# top.net
KiCad netlist of a schematic drawn in Altium Designer
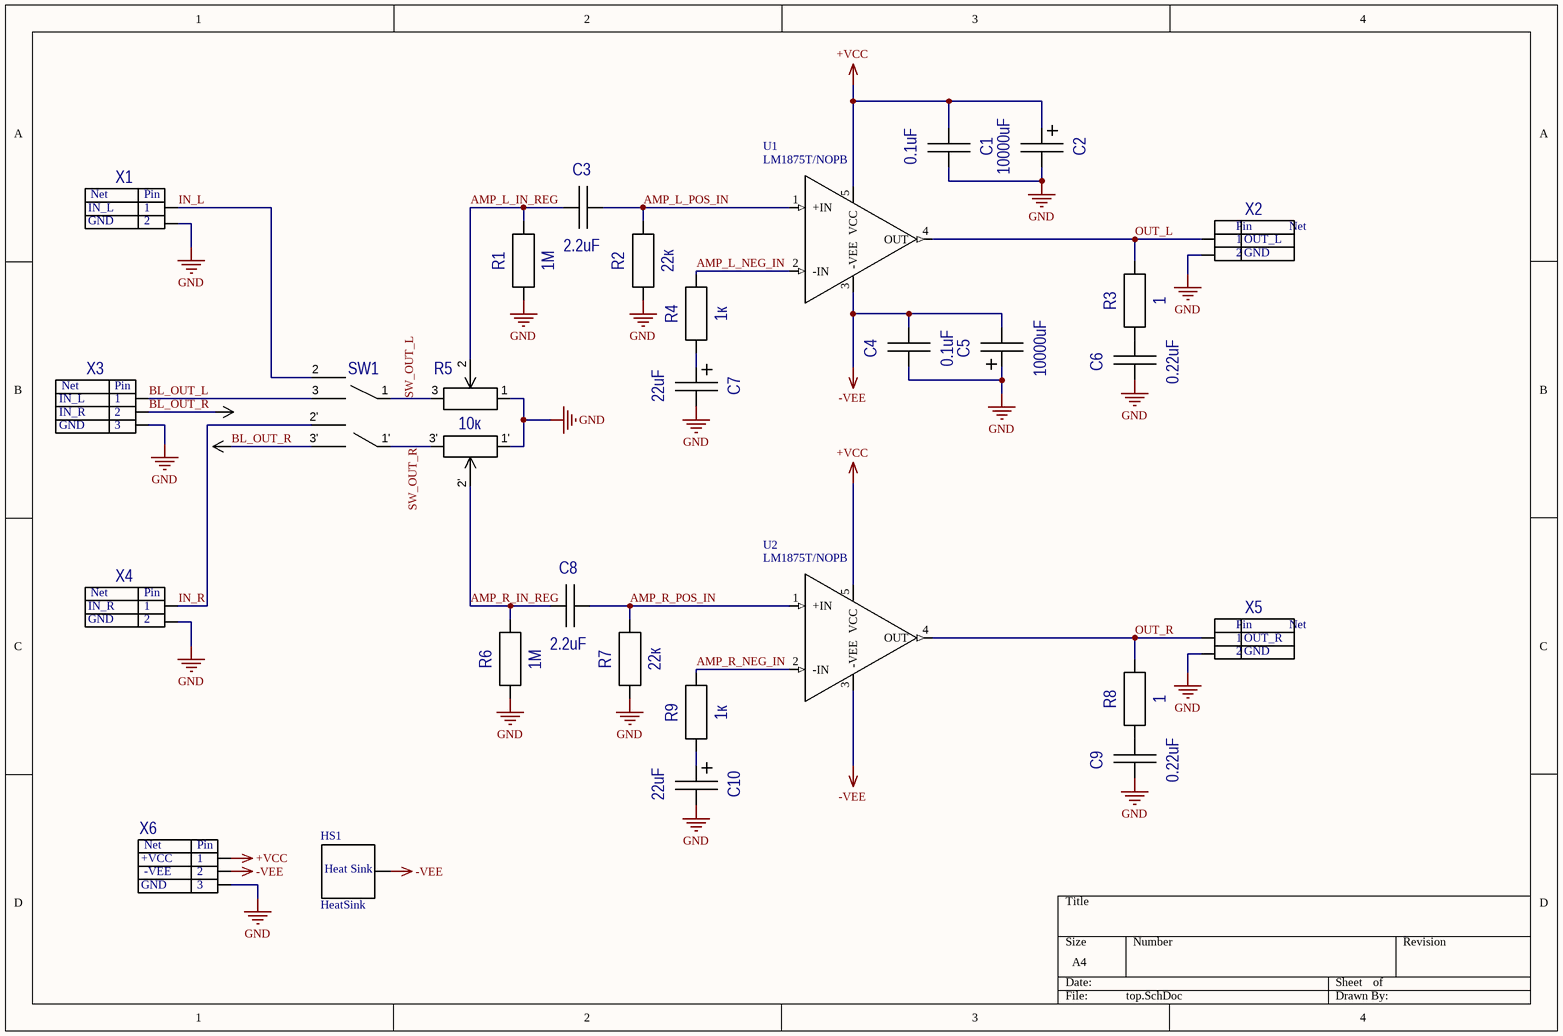
[diagram p0: top.SchDoc]

(export (version "E")
  (design (tool "Eeschema 10.0.6"))
  (components
    (comp (ref "C1")
      (value "0.1uF")
      (footprint "capK73-17")
      (description "26320")
      (libsource (lib "Schlib1") (part "К73-17, 0.1 мкФ, 250 В, 5%"))
    )
    (comp (ref "C2")
      (value "10000uF")
      (footprint "Capacitor_SnapIn_35x50mm")
      (description "26320")
      (libsource (lib "Schlib1") (part "ECAP (К50-35), 10000 мкФ, 50 В, 105°C, 20%"))
    )
    (comp (ref "C3")
      (value "2.2uF")
      (footprint "capK73-17")
      (description "8016")
      (libsource (lib "Schlib1") (part "К73-17, 2.2 мкФ, 63 В, 5%"))
    )
    (comp (ref "C4")
      (value "0.1uF")
      (footprint "capK73-17")
      (description "26320")
      (libsource (lib "Schlib1") (part "К73-17, 0.1 мкФ, 250 В, 5%"))
    )
    (comp (ref "C5")
      (value "10000uF")
      (footprint "Capacitor_SnapIn_35x50mm")
      (description "26320")
      (libsource (lib "Schlib1") (part "ECAP (К50-35), 10000 мкФ, 50 В, 105°C, 20%"))
    )
    (comp (ref "C6")
      (value "0.22uF")
      (footprint "capK73-17")
      (description "61862")
      (libsource (lib "Schlib1") (part "К73-17, 0.22 мкФ, 63 В, 5%"))
    )
    (comp (ref "C7")
      (value "22uF")
      (footprint "capRadial6.3x12mmP:2.5mm")
      (description "9000565851")
      (libsource (lib "Schlib1") (part "ECAP (К50-35), 10000 мкФ, 50 В, 105°C, 20%_1"))
    )
    (comp (ref "C8")
      (value "2.2uF")
      (footprint "capK73-17")
      (description "8016")
      (libsource (lib "Schlib1") (part "К73-17, 2.2 мкФ, 63 В, 5%"))
    )
    (comp (ref "C9")
      (value "0.22uF")
      (footprint "capK73-17")
      (description "61862")
      (libsource (lib "Schlib1") (part "К73-17, 0.22 мкФ, 63 В, 5%"))
    )
    (comp (ref "C10")
      (value "22uF")
      (footprint "capRadial6.3x12mmP:2.5mm")
      (description "9000565851")
      (libsource (lib "Schlib1") (part "ECAP (К50-35), 10000 мкФ, 50 В, 105°C, 20%_1"))
    )
    (comp (ref "HS1") (value "HeatSink") (footprint "HeatSink") (libsource (lib "Schlib1") (part "HeatSink")))
    (comp (ref "R1")
      (value "1М")
      (footprint "res0.25W/1M/0.5pitch")
      (description "51741")
      (libsource (lib "Schlib1") (part "CF-25 (С1-4) 0.25 Вт, 1 МОм, 5%"))
    )
    (comp (ref "R2")
      (value "22к")
      (footprint "res0.25W/22k/400mil")
      (description "8007031688")
      (libsource (lib "Schlib1") (part "1/4W22K, Резистор угольный 1/4Вт 22 кОм 2,5X7мм 5%"))
    )
    (comp (ref "R3")
      (value "1")
      (footprint "res1W/1/700mil")
      (description "24035")
      (libsource (lib "Schlib1") (part "MO-100 (С2-23) 1 Вт, 1 Ом, 5%"))
    )
    (comp (ref "R4")
      (value "1к")
      (footprint "res0.25W/1k/400mil")
      (description "44435")
      (libsource (lib "Schlib1") (part "CF-25 (С1-4) 0.25 Вт, 1 кОм, 5%"))
    )
    (comp (ref "R5")
      (value "10к")
      (footprint "dualVarRes")
      (description "588623436")
      (libsource (lib "Schlib1") (part "RK-1233G1-A10K, L15KC, 2 х 10 кОм"))
    )
    (comp (ref "R6")
      (value "1М")
      (footprint "res0.25W/1M/0.5pitch")
      (description "51741")
      (libsource (lib "Schlib1") (part "CF-25 (С1-4) 0.25 Вт, 1 МОм, 5%"))
    )
    (comp (ref "R7")
      (value "22к")
      (footprint "res0.25W/22k/400mil")
      (description "8007031688")
      (libsource (lib "Schlib1") (part "1/4W22K, Резистор угольный 1/4Вт 22 кОм 2,5X7мм 5%"))
    )
    (comp (ref "R8")
      (value "1")
      (footprint "res1W/1/700mil")
      (description "24035")
      (libsource (lib "Schlib1") (part "MO-100 (С2-23) 1 Вт, 1 Ом, 5%"))
    )
    (comp (ref "R9")
      (value "1к")
      (footprint "res0.25W/1k/400mil")
      (description "44435")
      (libsource (lib "Schlib1") (part "CF-25 (С1-4) 0.25 Вт, 1 кОм, 5%"))
    )
    (comp (ref "SW1") (value "~") (footprint "dualVarRes") (libsource (lib "Schlib1") (part "SWITCHER")))
    (comp (ref "U1")
      (value "LM1875T/NOPB")
      (footprint "TO220-5/2.54")
      (description "12717")
      (libsource (lib "Schlib1") (part "LM1875T/NOPB"))
    )
    (comp (ref "U2")
      (value "LM1875T/NOPB")
      (footprint "TO220-5/2.54")
      (description "12717")
      (libsource (lib "Schlib1") (part "LM1875T/NOPB"))
    )
    (comp (ref "X1")
      (value "~")
      (footprint "BUTTON_template")
      (description "Generic connector")
      (fields (field (name "PARAMETER 2") "IN_L") (field (name "PARAMETER 1") "GND"))
      (libsource (lib "Schlib1") (part "2pinConnector"))
    )
    (comp (ref "X2")
      (value "~")
      (footprint "BUTTON_template")
      (description "Generic connector")
      (fields (field (name "PARAMETER 2") "OUT_L") (field (name "PARAMETER 1") "GND"))
      (libsource (lib "Schlib1") (part "2pinConnector"))
    )
    (comp (ref "X3")
      (value "~")
      (footprint "3pim2.54Connector")
      (description "Input from Bluetooth module")
      (libsource (lib "Schlib1") (part "BluetoothModule"))
    )
    (comp (ref "X4")
      (value "~")
      (footprint "BUTTON_template")
      (description "Generic connector")
      (fields (field (name "PARAMETER 2") "IN_R") (field (name "PARAMETER 1") "GND"))
      (libsource (lib "Schlib1") (part "2pinConnector"))
    )
    (comp (ref "X5")
      (value "~")
      (footprint "BUTTON_template")
      (description "Generic connector")
      (fields (field (name "PARAMETER 2") "OUT_R") (field (name "PARAMETER 1") "GND"))
      (libsource (lib "Schlib1") (part "2pinConnector"))
    )
    (comp (ref "X6")
      (value "~")
      (footprint "3pim2.54Connector")
      (description "Generic connector")
      (fields
        (field (name "PARAMETER 3") "+VCC")
        (field (name "PARAMETER 2") "-VEE")
        (field (name "PARAMETER 1") "GND")
      )
      (libsource (lib "Schlib1") (part "3pinConnector"))
    )
  )
  (nets
    (net (code "1") (name "+VCC") (class "Default")
      (node (ref "C1") (pin "1") (pinfunction "1_1") (pintype "passive"))
      (node (ref "C2") (pin "1") (pinfunction "+_1") (pintype "passive"))
      (node (ref "U1") (pin "5") (pinfunction "VCC_5") (pintype "power_in"))
      (node (ref "U2") (pin "5") (pinfunction "VCC_5") (pintype "power_in"))
      (node (ref "X6") (pin "1") (pinfunction "1_1") (pintype "passive"))
    )
    (net (code "2") (name "-VEE") (class "Default")
      (node (ref "C4") (pin "2") (pinfunction "2_2") (pintype "passive"))
      (node (ref "C5") (pin "2") (pinfunction "-_2") (pintype "passive"))
      (node (ref "HS1") (pin "1") (pinfunction "HS_1") (pintype "power_in"))
      (node (ref "U1") (pin "3") (pinfunction "-VEE_3") (pintype "power_in"))
      (node (ref "U2") (pin "3") (pinfunction "-VEE_3") (pintype "power_in"))
      (node (ref "X6") (pin "2") (pinfunction "2_2") (pintype "passive"))
    )
    (net (code "3") (name "/AMP_L_IN_REG") (class "Default")
      (node (ref "C3") (pin "1") (pinfunction "1_1") (pintype "passive"))
      (node (ref "R1") (pin "2") (pinfunction "2_2") (pintype "passive"))
      (node (ref "R5") (pin "2") (pinfunction "2_2") (pintype "passive"))
    )
    (net (code "4") (name "/AMP_L_NEG_IN") (class "Default")
      (node (ref "R4") (pin "2") (pinfunction "2_2") (pintype "passive"))
      (node (ref "U1") (pin "2") (pinfunction "-IN_2") (pintype "input"))
    )
    (net (code "5") (name "/AMP_L_POS_IN") (class "Default")
      (node (ref "C3") (pin "2") (pinfunction "2_2") (pintype "passive"))
      (node (ref "R2") (pin "2") (pinfunction "2_2") (pintype "passive"))
      (node (ref "U1") (pin "1") (pinfunction "+IN_1") (pintype "input"))
    )
    (net (code "6") (name "/AMP_R_IN_REG") (class "Default")
      (node (ref "C8") (pin "1") (pinfunction "1_1") (pintype "passive"))
      (node (ref "R5") (pin "2'") (pinfunction "2'_2'") (pintype "passive"))
      (node (ref "R6") (pin "2") (pinfunction "2_2") (pintype "passive"))
    )
    (net (code "7") (name "/AMP_R_NEG_IN") (class "Default")
      (node (ref "R9") (pin "2") (pinfunction "2_2") (pintype "passive"))
      (node (ref "U2") (pin "2") (pinfunction "-IN_2") (pintype "input"))
    )
    (net (code "8") (name "/AMP_R_POS_IN") (class "Default")
      (node (ref "C8") (pin "2") (pinfunction "2_2") (pintype "passive"))
      (node (ref "R7") (pin "2") (pinfunction "2_2") (pintype "passive"))
      (node (ref "U2") (pin "1") (pinfunction "+IN_1") (pintype "input"))
    )
    (net (code "9") (name "/BL_OUT_L") (class "Default")
      (node (ref "SW1") (pin "3") (pinfunction "3_3") (pintype "passive"))
      (node (ref "X3") (pin "1") (pinfunction "1_1") (pintype "passive"))
    )
    (net (code "10") (name "/BL_OUT_R") (class "Default")
      (node (ref "SW1") (pin "3'") (pinfunction "3'_3'") (pintype "passive"))
      (node (ref "X3") (pin "2") (pinfunction "2_2") (pintype "passive"))
    )
    (net (code "11") (name "/IN_L") (class "Default")
      (node (ref "SW1") (pin "2") (pinfunction "2_2") (pintype "passive"))
      (node (ref "X1") (pin "1") (pinfunction "1_1") (pintype "passive"))
    )
    (net (code "12") (name "/IN_R") (class "Default")
      (node (ref "SW1") (pin "2'") (pinfunction "2'_2'") (pintype "passive"))
      (node (ref "X4") (pin "1") (pinfunction "1_1") (pintype "passive"))
    )
    (net (code "13") (name "/OUT_L") (class "Default")
      (node (ref "R3") (pin "2") (pinfunction "2_2") (pintype "passive"))
      (node (ref "U1") (pin "4") (pinfunction "OUT_4") (pintype "output"))
      (node (ref "X2") (pin "1") (pinfunction "1_1") (pintype "passive"))
    )
    (net (code "14") (name "/OUT_R") (class "Default")
      (node (ref "R8") (pin "2") (pinfunction "2_2") (pintype "passive"))
      (node (ref "U2") (pin "4") (pinfunction "OUT_4") (pintype "output"))
      (node (ref "X5") (pin "1") (pinfunction "1_1") (pintype "passive"))
    )
    (net (code "15") (name "/SW_OUT_L") (class "Default")
      (node (ref "R5") (pin "3") (pinfunction "3_3") (pintype "passive"))
      (node (ref "SW1") (pin "1") (pinfunction "1_1") (pintype "passive"))
    )
    (net (code "16") (name "/SW_OUT_R") (class "Default")
      (node (ref "R5") (pin "3'") (pinfunction "3'_3'") (pintype "passive"))
      (node (ref "SW1") (pin "1'") (pinfunction "1'_1'") (pintype "passive"))
    )
    (net (code "17") (name "GND") (class "Default")
      (node (ref "C1") (pin "2") (pinfunction "2_2") (pintype "passive"))
      (node (ref "C10") (pin "2") (pinfunction "-_2") (pintype "passive"))
      (node (ref "C2") (pin "2") (pinfunction "-_2") (pintype "passive"))
      (node (ref "C4") (pin "1") (pinfunction "1_1") (pintype "passive"))
      (node (ref "C5") (pin "1") (pinfunction "+_1") (pintype "passive"))
      (node (ref "C6") (pin "1") (pinfunction "1_1") (pintype "passive"))
      (node (ref "C7") (pin "2") (pinfunction "-_2") (pintype "passive"))
      (node (ref "C9") (pin "1") (pinfunction "1_1") (pintype "passive"))
      (node (ref "R1") (pin "1") (pinfunction "1_1") (pintype "passive"))
      (node (ref "R2") (pin "1") (pinfunction "1_1") (pintype "passive"))
      (node (ref "R5") (pin "1") (pinfunction "1_1") (pintype "passive"))
      (node (ref "R5") (pin "1'") (pinfunction "1'_1'") (pintype "passive"))
      (node (ref "R6") (pin "1") (pinfunction "1_1") (pintype "passive"))
      (node (ref "R7") (pin "1") (pinfunction "1_1") (pintype "passive"))
      (node (ref "X1") (pin "2") (pinfunction "2_2") (pintype "passive"))
      (node (ref "X2") (pin "2") (pinfunction "2_2") (pintype "passive"))
      (node (ref "X3") (pin "3") (pinfunction "3_3") (pintype "passive"))
      (node (ref "X4") (pin "2") (pinfunction "2_2") (pintype "passive"))
      (node (ref "X5") (pin "2") (pinfunction "2_2") (pintype "passive"))
      (node (ref "X6") (pin "3") (pinfunction "3_3") (pintype "passive"))
    )
    (net (code "18") (name "Net-(C6-Pad2)") (class "Default")
      (node (ref "C6") (pin "2") (pinfunction "2_2") (pintype "passive"))
      (node (ref "R3") (pin "1") (pinfunction "1_1") (pintype "passive"))
    )
    (net (code "19") (name "Net-(C7-+)") (class "Default")
      (node (ref "C7") (pin "1") (pinfunction "+_1") (pintype "passive"))
      (node (ref "R4") (pin "1") (pinfunction "1_1") (pintype "passive"))
    )
    (net (code "20") (name "Net-(C9-Pad2)") (class "Default")
      (node (ref "C9") (pin "2") (pinfunction "2_2") (pintype "passive"))
      (node (ref "R8") (pin "1") (pinfunction "1_1") (pintype "passive"))
    )
    (net (code "21") (name "Net-(C10-+)") (class "Default")
      (node (ref "C10") (pin "1") (pinfunction "+_1") (pintype "passive"))
      (node (ref "R9") (pin "1") (pinfunction "1_1") (pintype "passive"))
    )
  )
)
